# MPU6050_version_2.net
KiCad netlist of a schematic drawn in EAGLE
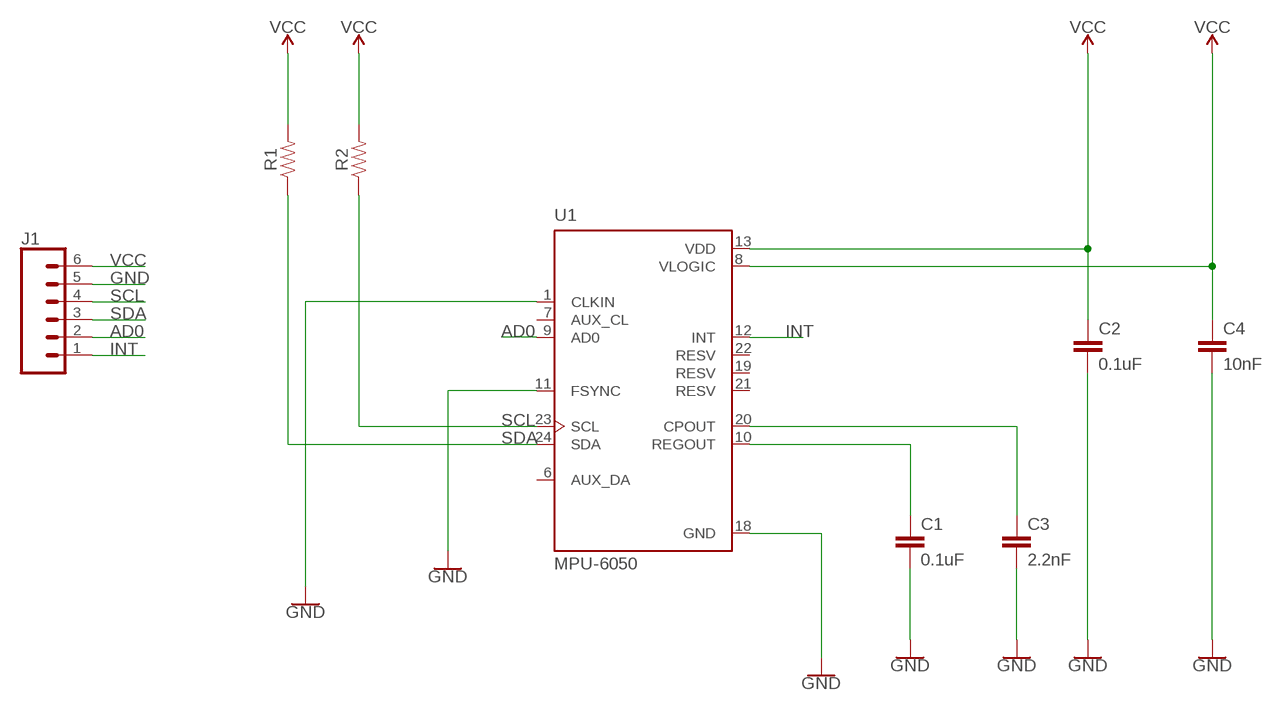
[diagram p0: schematic, sheet 1]

(export (version "E")
  (design (tool "Eeschema 10.0.6"))
  (components
    (comp (ref "C1")
      (value "0.1uF")
      (footprint "eagle-import:0805")
      (libsource (lib "eagle-import") (part "1.0UF-0805-25V-10%"))
    )
    (comp (ref "C2")
      (value "0.1uF")
      (footprint "eagle-import:0805")
      (libsource (lib "eagle-import") (part "1.0UF-0805-25V-10%"))
    )
    (comp (ref "C3")
      (value "2.2nF")
      (footprint "eagle-import:0805")
      (libsource (lib "eagle-import") (part "1.0UF-0805-25V-10%"))
    )
    (comp (ref "C4")
      (value "10nF")
      (footprint "eagle-import:0805")
      (libsource (lib "eagle-import") (part "1.0UF-0805-25V-10%"))
    )
    (comp (ref "J1")
      (value "CONN_06NO_SILK_FEMALE_PTH")
      (footprint "eagle-import:1X06_NO_SILK")
      (libsource (lib "eagle-import") (part "CONN_06NO_SILK_FEMALE_PTH"))
    )
    (comp (ref "R1")
      (value "RESISTOR0805")
      (footprint "eagle-import:0805")
      (libsource (lib "eagle-import") (part "RESISTOR0805"))
    )
    (comp (ref "R2")
      (value "RESISTOR0805")
      (footprint "eagle-import:0805")
      (libsource (lib "eagle-import") (part "RESISTOR0805"))
    )
    (comp (ref "U1")
      (value "MPU-6050")
      (footprint "eagle-import:QFN50P400X400X95-24N")
      (fields (field (name "DIGI-KEY_PART_NUMBER") "1428-1007-1-ND") (field (name "MF") "TDK InvenSense"))
      (libsource (lib "eagle-import") (part "MPU-6050"))
    )
  )
  (nets
    (net (code "1") (name "/AD0") (class "Default")
      (node (ref "J1") (pin "2") (pinfunction "2_2") (pintype "passive"))
      (node (ref "U1") (pin "9") (pinfunction "AD0_9") (pintype "input"))
    )
    (net (code "2") (name "/INT") (class "Default")
      (node (ref "J1") (pin "1") (pinfunction "1_1") (pintype "passive"))
      (node (ref "U1") (pin "12") (pinfunction "INT_12") (pintype "output"))
    )
    (net (code "3") (name "/SCL") (class "Default")
      (node (ref "J1") (pin "4") (pinfunction "4_4") (pintype "passive"))
      (node (ref "R2") (pin "1") (pinfunction "1_1") (pintype "passive"))
      (node (ref "U1") (pin "23") (pinfunction "SCL_23") (pintype "input"))
    )
    (net (code "4") (name "/SDA") (class "Default")
      (node (ref "J1") (pin "3") (pinfunction "3_3") (pintype "passive"))
      (node (ref "R1") (pin "1") (pinfunction "1_1") (pintype "passive"))
      (node (ref "U1") (pin "24") (pinfunction "SDA_24") (pintype "bidirectional"))
    )
    (net (code "5") (name "GND") (class "Default")
      (node (ref "C1") (pin "2") (pinfunction "2_2") (pintype "passive"))
      (node (ref "C2") (pin "2") (pinfunction "2_2") (pintype "passive"))
      (node (ref "C3") (pin "2") (pinfunction "2_2") (pintype "passive"))
      (node (ref "C4") (pin "2") (pinfunction "2_2") (pintype "passive"))
      (node (ref "J1") (pin "5") (pinfunction "5_5") (pintype "passive"))
      (node (ref "U1") (pin "1") (pinfunction "CLKIN_1") (pintype "input"))
      (node (ref "U1") (pin "11") (pinfunction "FSYNC_11") (pintype "input"))
      (node (ref "U1") (pin "18") (pinfunction "GND_18") (pintype "power_in"))
    )
    (net (code "6") (name "Net-(U1-CPOUT)") (class "Default")
      (node (ref "C3") (pin "1") (pinfunction "1_1") (pintype "passive"))
      (node (ref "U1") (pin "20") (pinfunction "CPOUT_20") (pintype "passive"))
    )
    (net (code "7") (name "Net-(U1-REGOUT)") (class "Default")
      (node (ref "C1") (pin "1") (pinfunction "1_1") (pintype "passive"))
      (node (ref "U1") (pin "10") (pinfunction "REGOUT_10") (pintype "passive"))
    )
    (net (code "8") (name "VCC") (class "Default")
      (node (ref "C2") (pin "1") (pinfunction "1_1") (pintype "passive"))
      (node (ref "C4") (pin "1") (pinfunction "1_1") (pintype "passive"))
      (node (ref "J1") (pin "6") (pinfunction "6_6") (pintype "passive"))
      (node (ref "R1") (pin "2") (pinfunction "2_2") (pintype "passive"))
      (node (ref "R2") (pin "2") (pinfunction "2_2") (pintype "passive"))
      (node (ref "U1") (pin "13") (pinfunction "VDD_13") (pintype "power_in"))
      (node (ref "U1") (pin "8") (pinfunction "VLOGIC_8") (pintype "power_in"))
    )
    (net (code "9") (name "unconnected-(U1-AUX_CL-Pad7)") (class "Default")
      (node (ref "U1") (pin "7") (pinfunction "AUX_CL_7") (pintype "input"))
    )
    (net (code "10") (name "unconnected-(U1-AUX_DA-Pad6)") (class "Default")
      (node (ref "U1") (pin "6") (pinfunction "AUX_DA_6") (pintype "bidirectional"))
    )
    (net (code "11") (name "unconnected-(U1-RESV-Pad19)") (class "Default")
      (node (ref "U1") (pin "19") (pinfunction "RESV_19") (pintype "passive"))
    )
    (net (code "12") (name "unconnected-(U1-RESV-Pad21)") (class "Default")
      (node (ref "U1") (pin "21") (pinfunction "RESV_21") (pintype "passive"))
    )
    (net (code "13") (name "unconnected-(U1-RESV-Pad22)") (class "Default")
      (node (ref "U1") (pin "22") (pinfunction "RESV_22") (pintype "passive"))
    )
  )
)
